# Hardwiring.net
KiCad netlist of a schematic drawn in Altium Designer
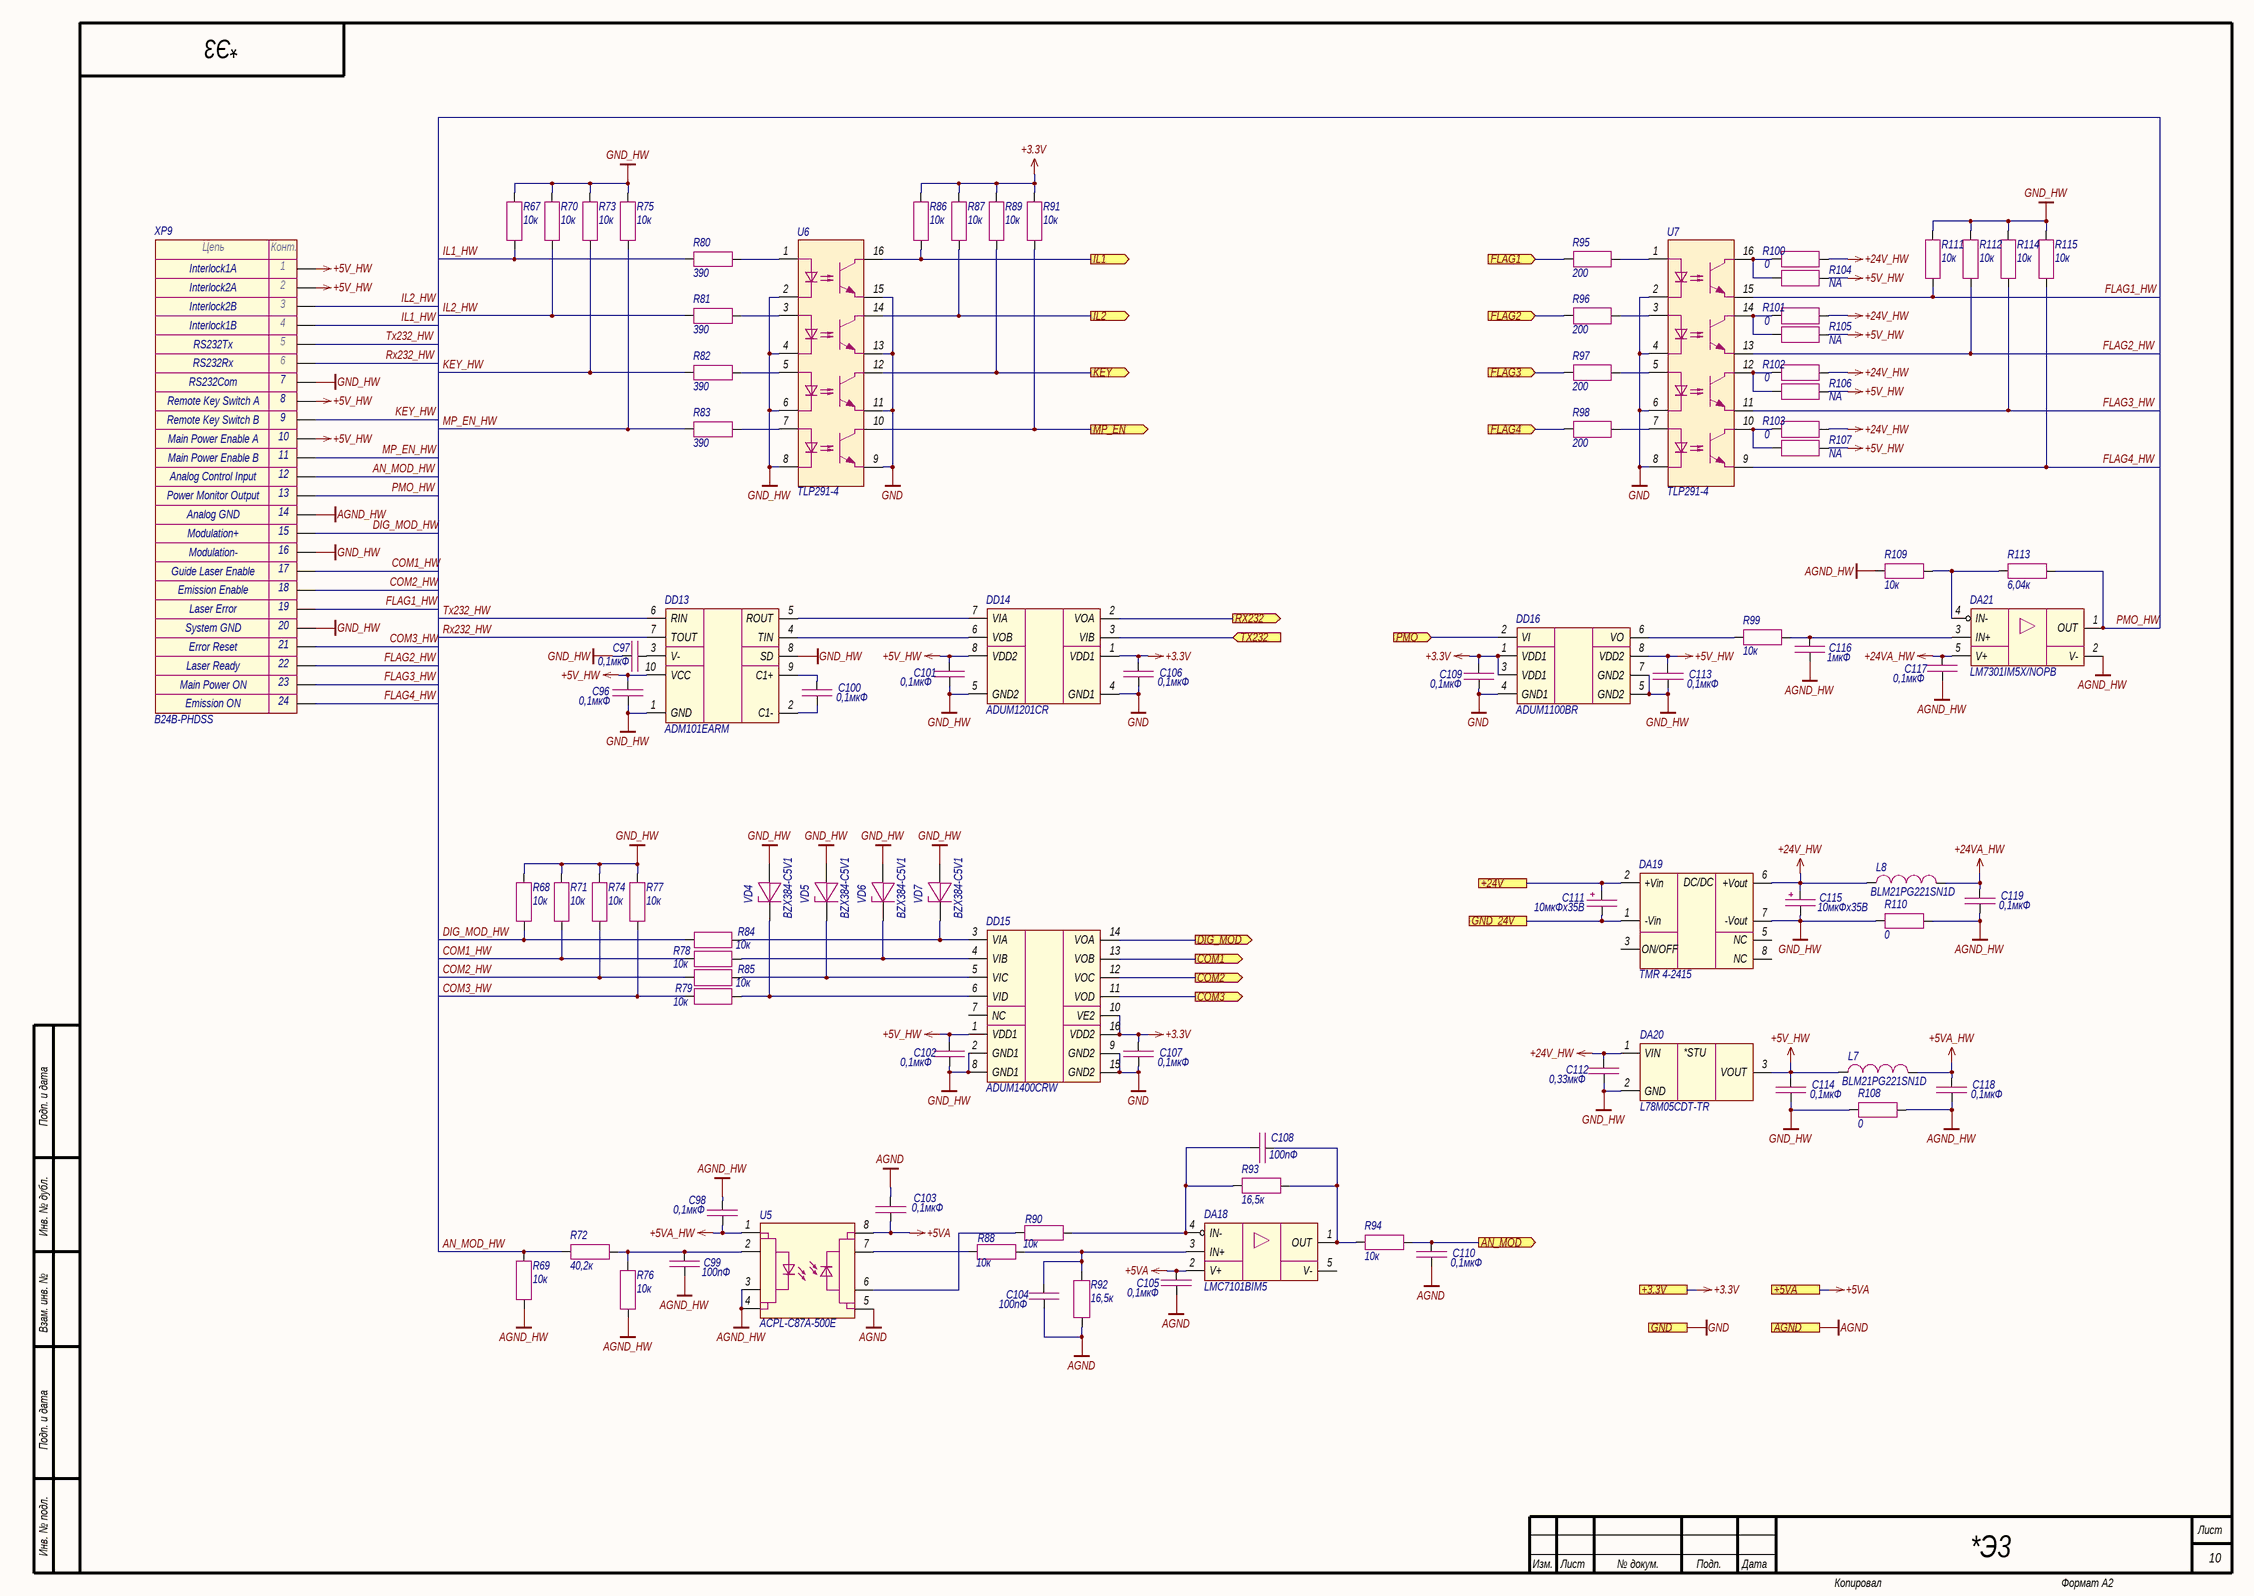
[diagram p0: Hardwiring.SchDoc]

(export (version "E")
  (design (tool "Eeschema 10.0.6"))
  (components
    (comp (ref "C96")
      (value "0,1мкФ")
      (footprint "Pcb_library:CAP_0603")
      (fields (field (name "MANUFACTURER") "Murata"))
      (libsource (lib "Schem_library") (part "Capacitor"))
    )
    (comp (ref "C97")
      (value "0,1мкФ")
      (footprint "Pcb_library:CAP_0603")
      (fields (field (name "MANUFACTURER") "Murata"))
      (libsource (lib "Schem_library") (part "Capacitor"))
    )
    (comp (ref "C98")
      (value "0,1мкФ")
      (footprint "Pcb_library:CAP_0603")
      (fields (field (name "MANUFACTURER") "Murata"))
      (libsource (lib "Schem_library") (part "Capacitor"))
    )
    (comp (ref "C99")
      (value "100пФ")
      (footprint "Pcb_library:CAP_0603")
      (fields (field (name "MANUFACTURER") "Murata"))
      (libsource (lib "Schem_library") (part "Capacitor"))
    )
    (comp (ref "C100")
      (value "0,1мкФ")
      (footprint "Pcb_library:CAP_0603")
      (fields (field (name "MANUFACTURER") "Murata"))
      (libsource (lib "Schem_library") (part "Capacitor"))
    )
    (comp (ref "C101")
      (value "0,1мкФ")
      (footprint "Pcb_library:CAP_0603")
      (fields (field (name "MANUFACTURER") "Murata"))
      (libsource (lib "Schem_library") (part "Capacitor"))
    )
    (comp (ref "C102")
      (value "0,1мкФ")
      (footprint "Pcb_library:CAP_0603")
      (fields (field (name "MANUFACTURER") "Murata"))
      (libsource (lib "Schem_library") (part "Capacitor"))
    )
    (comp (ref "C103")
      (value "0,1мкФ")
      (footprint "Pcb_library:CAP_0603")
      (fields (field (name "MANUFACTURER") "Murata"))
      (libsource (lib "Schem_library") (part "Capacitor"))
    )
    (comp (ref "C104")
      (value "100пФ")
      (footprint "Pcb_library:CAP_0603")
      (fields (field (name "MANUFACTURER") "Murata"))
      (libsource (lib "Schem_library") (part "Capacitor"))
    )
    (comp (ref "C105")
      (value "0,1мкФ")
      (footprint "Pcb_library:CAP_0603")
      (fields (field (name "MANUFACTURER") "Murata"))
      (libsource (lib "Schem_library") (part "Capacitor"))
    )
    (comp (ref "C106")
      (value "0,1мкФ")
      (footprint "Pcb_library:CAP_0603")
      (fields (field (name "MANUFACTURER") "Murata"))
      (libsource (lib "Schem_library") (part "Capacitor"))
    )
    (comp (ref "C107")
      (value "0,1мкФ")
      (footprint "Pcb_library:CAP_0603")
      (fields (field (name "MANUFACTURER") "Murata"))
      (libsource (lib "Schem_library") (part "Capacitor"))
    )
    (comp (ref "C108")
      (value "100пФ")
      (footprint "Pcb_library:CAP_0603")
      (fields (field (name "MANUFACTURER") "Murata"))
      (libsource (lib "Schem_library") (part "Capacitor"))
    )
    (comp (ref "C109")
      (value "0,1мкФ")
      (footprint "Pcb_library:CAP_0603")
      (fields (field (name "MANUFACTURER") "Murata"))
      (libsource (lib "Schem_library") (part "Capacitor"))
    )
    (comp (ref "C110")
      (value "0,1мкФ")
      (footprint "Pcb_library:CAP_0603")
      (fields (field (name "MANUFACTURER") "Murata"))
      (libsource (lib "Schem_library") (part "Capacitor"))
    )
    (comp (ref "C111")
      (value "10мкФх35B")
      (footprint "Pcb_library:CAP_C")
      (libsource (lib "Schem_library") (part "Capacitor_Polar"))
    )
    (comp (ref "C112")
      (value "0,33мкФ")
      (footprint "Pcb_library:CAP_0805")
      (fields (field (name "MANUFACTURER") "Murata"))
      (libsource (lib "Schem_library") (part "Capacitor"))
    )
    (comp (ref "C113")
      (value "0,1мкФ")
      (footprint "Pcb_library:CAP_0603")
      (fields (field (name "MANUFACTURER") "Murata"))
      (libsource (lib "Schem_library") (part "Capacitor"))
    )
    (comp (ref "C114")
      (value "0,1мкФ")
      (footprint "Pcb_library:CAP_0603")
      (fields (field (name "MANUFACTURER") "Murata"))
      (libsource (lib "Schem_library") (part "Capacitor"))
    )
    (comp (ref "C115")
      (value "10мкФх35B")
      (footprint "Pcb_library:CAP_C")
      (libsource (lib "") (part "Capacitor_Polar_1"))
    )
    (comp (ref "C116")
      (value "1мкФ")
      (footprint "Pcb_library:CAP_0603")
      (fields (field (name "MANUFACTURER") "Murata"))
      (libsource (lib "Schem_library") (part "Capacitor"))
    )
    (comp (ref "C117")
      (value "0,1мкФ")
      (footprint "Pcb_library:CAP_0603")
      (fields (field (name "MANUFACTURER") "Murata"))
      (libsource (lib "Schem_library") (part "Capacitor"))
    )
    (comp (ref "C118")
      (value "0,1мкФ")
      (footprint "Pcb_library:CAP_0603")
      (fields (field (name "MANUFACTURER") "Murata"))
      (libsource (lib "Schem_library") (part "Capacitor"))
    )
    (comp (ref "C119")
      (value "0,1мкФ")
      (footprint "Pcb_library:CAP_0603")
      (fields (field (name "MANUFACTURER") "Murata"))
      (libsource (lib "Schem_library") (part "Capacitor"))
    )
    (comp (ref "DA18")
      (value "LMC7101BIM5")
      (footprint "Pcb_library:SOT-23-5")
      (fields (field (name "MANUFACTURER") "Texas Instruments"))
      (libsource (lib "Schem_library") (part "LMC7101"))
    )
    (comp (ref "DA19")
      (value "TMR 4-2415")
      (footprint "Pcb_library:TMR4 (SIP-8)")
      (fields (field (name "MANUFACTURER") "Traco Power"))
      (libsource (lib "Schem_library") (part "TMR4"))
    )
    (comp (ref "DA20")
      (value "L78M05CDT-TR")
      (footprint "Pcb_library:TO-252")
      (fields (field (name "MANUFACTURER") "STMicroelectronics"))
      (libsource (lib "Schem_library") (part "L78M"))
    )
    (comp (ref "DA21")
      (value "LM7301IM5X/NOPB")
      (footprint "Pcb_library:SOT-23-5")
      (fields (field (name "MANUFACTURER") "Texas Instruments"))
      (libsource (lib "Schem_library") (part "LM7301IM5"))
    )
    (comp (ref "DD13")
      (value "ADM101EARM")
      (footprint "Pcb_library:MSOP-10")
      (fields (field (name "MANUFACTURER") "Analog Devices"))
      (libsource (lib "Schem_library") (part "ADM101EARM"))
    )
    (comp (ref "DD14")
      (value "ADUM1201CR")
      (footprint "Pcb_library:SOIC-8")
      (fields (field (name "MANUFACTURER") "Analog Devices"))
      (libsource (lib "Schem_library") (part "ADUM1201"))
    )
    (comp (ref "DD15")
      (value "ADUM1400CRW")
      (footprint "Pcb_library:SOIC-16W")
      (fields (field (name "MANUFACTURER") "Analog Devices"))
      (libsource (lib "Schem_library") (part "ADUM1400"))
    )
    (comp (ref "DD16")
      (value "ADUM1100BR")
      (footprint "Pcb_library:SOIC-8")
      (fields (field (name "MANUFACTURER") "Analog Devices"))
      (libsource (lib "Schem_library") (part "ADUM1100"))
    )
    (comp (ref "L7")
      (value "BLM21PG221SN1D")
      (footprint "Pcb_library:IND_0805")
      (fields (field (name "MANUFACTURER") "Murata"))
      (libsource (lib "Schem_library") (part "Inductor"))
    )
    (comp (ref "L8")
      (value "BLM21PG221SN1D")
      (footprint "Pcb_library:IND_0805")
      (fields (field (name "MANUFACTURER") "Murata"))
      (libsource (lib "Schem_library") (part "Inductor"))
    )
    (comp (ref "R67")
      (value "10к")
      (footprint "Pcb_library:RES_0603")
      (fields (field (name "MANUFACTURER") "Yageo"))
      (libsource (lib "Schem_library") (part "Resistor"))
    )
    (comp (ref "R68")
      (value "10к")
      (footprint "Pcb_library:RES_0603")
      (fields (field (name "MANUFACTURER") "Yageo"))
      (libsource (lib "Schem_library") (part "Resistor"))
    )
    (comp (ref "R69")
      (value "10к")
      (footprint "Pcb_library:RES_0603")
      (fields (field (name "MANUFACTURER") "Yageo"))
      (libsource (lib "Schem_library") (part "Resistor"))
    )
    (comp (ref "R70")
      (value "10к")
      (footprint "Pcb_library:RES_0603")
      (fields (field (name "MANUFACTURER") "Yageo"))
      (libsource (lib "Schem_library") (part "Resistor"))
    )
    (comp (ref "R71")
      (value "10к")
      (footprint "Pcb_library:RES_0603")
      (fields (field (name "MANUFACTURER") "Yageo"))
      (libsource (lib "Schem_library") (part "Resistor"))
    )
    (comp (ref "R72")
      (value "40,2к")
      (footprint "Pcb_library:RES_0603")
      (fields (field (name "MANUFACTURER") "Yageo"))
      (libsource (lib "Schem_library") (part "Resistor"))
    )
    (comp (ref "R73")
      (value "10к")
      (footprint "Pcb_library:RES_0603")
      (fields (field (name "MANUFACTURER") "Yageo"))
      (libsource (lib "Schem_library") (part "Resistor"))
    )
    (comp (ref "R74")
      (value "10к")
      (footprint "Pcb_library:RES_0603")
      (fields (field (name "MANUFACTURER") "Yageo"))
      (libsource (lib "Schem_library") (part "Resistor"))
    )
    (comp (ref "R75")
      (value "10к")
      (footprint "Pcb_library:RES_0603")
      (fields (field (name "MANUFACTURER") "Yageo"))
      (libsource (lib "Schem_library") (part "Resistor"))
    )
    (comp (ref "R76")
      (value "10к")
      (footprint "Pcb_library:RES_0603")
      (fields (field (name "MANUFACTURER") "Yageo"))
      (libsource (lib "Schem_library") (part "Resistor"))
    )
    (comp (ref "R77")
      (value "10к")
      (footprint "Pcb_library:RES_0603")
      (fields (field (name "MANUFACTURER") "Yageo"))
      (libsource (lib "Schem_library") (part "Resistor"))
    )
    (comp (ref "R78")
      (value "10к")
      (footprint "Pcb_library:RES_0603")
      (fields (field (name "MANUFACTURER") "Yageo"))
      (libsource (lib "Schem_library") (part "Resistor"))
    )
    (comp (ref "R79")
      (value "10к")
      (footprint "Pcb_library:RES_0603")
      (fields (field (name "MANUFACTURER") "Yageo"))
      (libsource (lib "Schem_library") (part "Resistor"))
    )
    (comp (ref "R80")
      (value "390")
      (footprint "Pcb_library:RES_0603")
      (fields (field (name "MANUFACTURER") "Yageo"))
      (libsource (lib "Schem_library") (part "Resistor"))
    )
    (comp (ref "R81")
      (value "390")
      (footprint "Pcb_library:RES_0603")
      (fields (field (name "MANUFACTURER") "Yageo"))
      (libsource (lib "Schem_library") (part "Resistor"))
    )
    (comp (ref "R82")
      (value "390")
      (footprint "Pcb_library:RES_0603")
      (fields (field (name "MANUFACTURER") "Yageo"))
      (libsource (lib "Schem_library") (part "Resistor"))
    )
    (comp (ref "R83")
      (value "390")
      (footprint "Pcb_library:RES_0603")
      (fields (field (name "MANUFACTURER") "Yageo"))
      (libsource (lib "Schem_library") (part "Resistor"))
    )
    (comp (ref "R84")
      (value "10к")
      (footprint "Pcb_library:RES_0603")
      (fields (field (name "MANUFACTURER") "Yageo"))
      (libsource (lib "Schem_library") (part "Resistor"))
    )
    (comp (ref "R85")
      (value "10к")
      (footprint "Pcb_library:RES_0603")
      (fields (field (name "MANUFACTURER") "Yageo"))
      (libsource (lib "Schem_library") (part "Resistor"))
    )
    (comp (ref "R86")
      (value "10к")
      (footprint "Pcb_library:RES_0603")
      (fields (field (name "MANUFACTURER") "Yageo"))
      (libsource (lib "Schem_library") (part "Resistor"))
    )
    (comp (ref "R87")
      (value "10к")
      (footprint "Pcb_library:RES_0603")
      (fields (field (name "MANUFACTURER") "Yageo"))
      (libsource (lib "Schem_library") (part "Resistor"))
    )
    (comp (ref "R88")
      (value "10к")
      (footprint "Pcb_library:RES_0603")
      (fields (field (name "MANUFACTURER") "Yageo"))
      (libsource (lib "Schem_library") (part "Resistor"))
    )
    (comp (ref "R89")
      (value "10к")
      (footprint "Pcb_library:RES_0603")
      (fields (field (name "MANUFACTURER") "Yageo"))
      (libsource (lib "Schem_library") (part "Resistor"))
    )
    (comp (ref "R90")
      (value "10к")
      (footprint "Pcb_library:RES_0603")
      (fields (field (name "MANUFACTURER") "Yageo"))
      (libsource (lib "Schem_library") (part "Resistor"))
    )
    (comp (ref "R91")
      (value "10к")
      (footprint "Pcb_library:RES_0603")
      (fields (field (name "MANUFACTURER") "Yageo"))
      (libsource (lib "Schem_library") (part "Resistor"))
    )
    (comp (ref "R92")
      (value "16,5к")
      (footprint "Pcb_library:RES_0603")
      (fields (field (name "MANUFACTURER") "Yageo"))
      (libsource (lib "Schem_library") (part "Resistor"))
    )
    (comp (ref "R93")
      (value "16,5к")
      (footprint "Pcb_library:RES_0603")
      (fields (field (name "MANUFACTURER") "Yageo"))
      (libsource (lib "Schem_library") (part "Resistor"))
    )
    (comp (ref "R94")
      (value "10к")
      (footprint "Pcb_library:RES_0603")
      (fields (field (name "MANUFACTURER") "Yageo"))
      (libsource (lib "Schem_library") (part "Resistor"))
    )
    (comp (ref "R95")
      (value "200")
      (footprint "Pcb_library:RES_0603")
      (fields (field (name "MANUFACTURER") "Yageo"))
      (libsource (lib "Schem_library") (part "Resistor"))
    )
    (comp (ref "R96")
      (value "200")
      (footprint "Pcb_library:RES_0603")
      (fields (field (name "MANUFACTURER") "Yageo"))
      (libsource (lib "Schem_library") (part "Resistor"))
    )
    (comp (ref "R97")
      (value "200")
      (footprint "Pcb_library:RES_0603")
      (fields (field (name "MANUFACTURER") "Yageo"))
      (libsource (lib "Schem_library") (part "Resistor"))
    )
    (comp (ref "R98")
      (value "200")
      (footprint "Pcb_library:RES_0603")
      (fields (field (name "MANUFACTURER") "Yageo"))
      (libsource (lib "Schem_library") (part "Resistor"))
    )
    (comp (ref "R99")
      (value "10к")
      (footprint "Pcb_library:RES_0603")
      (fields (field (name "MANUFACTURER") "Yageo"))
      (libsource (lib "Schem_library") (part "Resistor"))
    )
    (comp (ref "R100")
      (value "0")
      (footprint "Pcb_library:RES_0603")
      (fields (field (name "MANUFACTURER") "Yageo"))
      (libsource (lib "Schem_library") (part "Resistor"))
    )
    (comp (ref "R101")
      (value "0")
      (footprint "Pcb_library:RES_0603")
      (fields (field (name "MANUFACTURER") "Yageo"))
      (libsource (lib "Schem_library") (part "Resistor"))
    )
    (comp (ref "R102")
      (value "0")
      (footprint "Pcb_library:RES_0603")
      (fields (field (name "MANUFACTURER") "Yageo"))
      (libsource (lib "Schem_library") (part "Resistor"))
    )
    (comp (ref "R103")
      (value "0")
      (footprint "Pcb_library:RES_0603")
      (fields (field (name "MANUFACTURER") "Yageo"))
      (libsource (lib "Schem_library") (part "Resistor"))
    )
    (comp (ref "R104")
      (value "NA")
      (footprint "Pcb_library:RES_0603")
      (libsource (lib "Schem_library") (part "Resistor"))
    )
    (comp (ref "R105")
      (value "NA")
      (footprint "Pcb_library:RES_0603")
      (libsource (lib "Schem_library") (part "Resistor"))
    )
    (comp (ref "R106")
      (value "NA")
      (footprint "Pcb_library:RES_0603")
      (libsource (lib "Schem_library") (part "Resistor"))
    )
    (comp (ref "R107")
      (value "NA")
      (footprint "Pcb_library:RES_0603")
      (libsource (lib "Schem_library") (part "Resistor"))
    )
    (comp (ref "R108")
      (value "0")
      (footprint "Pcb_library:RES_0805")
      (fields (field (name "MANUFACTURER") "Yageo"))
      (libsource (lib "Schem_library") (part "Resistor"))
    )
    (comp (ref "R109")
      (value "10к")
      (footprint "Pcb_library:RES_0603")
      (fields (field (name "MANUFACTURER") "Yageo"))
      (libsource (lib "Schem_library") (part "Resistor"))
    )
    (comp (ref "R110")
      (value "0")
      (footprint "Pcb_library:RES_0805")
      (fields (field (name "MANUFACTURER") "Yageo"))
      (libsource (lib "Schem_library") (part "Resistor"))
    )
    (comp (ref "R111")
      (value "10к")
      (footprint "Pcb_library:RES_0603")
      (fields (field (name "MANUFACTURER") "Yageo"))
      (libsource (lib "Schem_library") (part "Resistor"))
    )
    (comp (ref "R112")
      (value "10к")
      (footprint "Pcb_library:RES_0603")
      (fields (field (name "MANUFACTURER") "Yageo"))
      (libsource (lib "Schem_library") (part "Resistor"))
    )
    (comp (ref "R113")
      (value "6,04к")
      (footprint "Pcb_library:RES_0603")
      (fields (field (name "MANUFACTURER") "Yageo"))
      (libsource (lib "Schem_library") (part "Resistor"))
    )
    (comp (ref "R114")
      (value "10к")
      (footprint "Pcb_library:RES_0603")
      (fields (field (name "MANUFACTURER") "Yageo"))
      (libsource (lib "Schem_library") (part "Resistor"))
    )
    (comp (ref "R115")
      (value "10к")
      (footprint "Pcb_library:RES_0603")
      (fields (field (name "MANUFACTURER") "Yageo"))
      (libsource (lib "Schem_library") (part "Resistor"))
    )
    (comp (ref "U5")
      (value "ACPL-C87A-500E")
      (footprint "Pcb_library:SSO-8")
      (fields (field (name "MANUFACTURER") "Broadcom"))
      (libsource (lib "Schem_library") (part "ACPL-C87"))
    )
    (comp (ref "U6")
      (value "TLP291-4")
      (footprint "Pcb_library:SOP-16")
      (fields (field (name "MANUFACTURER") "Toshiba"))
      (libsource (lib "Schem_library") (part "TLP281-4"))
    )
    (comp (ref "U7")
      (value "TLP291-4")
      (footprint "Pcb_library:SOP-16")
      (fields (field (name "MANUFACTURER") "Toshiba"))
      (libsource (lib "Schem_library") (part "TLP281-4"))
    )
    (comp (ref "VD4")
      (value "BZX384-C5V1")
      (footprint "Pcb_library:SOD-323")
      (fields (field (name "MANUFACTURER") "Nexperia"))
      (libsource (lib "Schem_library") (part "Diode_Zener"))
    )
    (comp (ref "VD5")
      (value "BZX384-C5V1")
      (footprint "Pcb_library:SOD-323")
      (fields (field (name "MANUFACTURER") "Nexperia"))
      (libsource (lib "Schem_library") (part "Diode_Zener"))
    )
    (comp (ref "VD6")
      (value "BZX384-C5V1")
      (footprint "Pcb_library:SOD-323")
      (fields (field (name "MANUFACTURER") "Nexperia"))
      (libsource (lib "Schem_library") (part "Diode_Zener"))
    )
    (comp (ref "VD7")
      (value "BZX384-C5V1")
      (footprint "Pcb_library:SOD-323")
      (fields (field (name "MANUFACTURER") "Nexperia"))
      (libsource (lib "Schem_library") (part "Diode_Zener"))
    )
    (comp (ref "XP9")
      (value "B24B-PHDSS")
      (footprint "Pcb_library:B24B-PHDSS")
      (fields (field (name "MANUFACTURER") "JST"))
      (libsource (lib "Schem_library") (part "Connector-24"))
    )
  )
  (nets
    (net (code "1") (name "+3.3V") (class "Default")
      (node (ref "C106") (pin "1") (pinfunction "1_1") (pintype "passive"))
      (node (ref "C107") (pin "1") (pinfunction "1_1") (pintype "passive"))
      (node (ref "C109") (pin "1") (pinfunction "1_1") (pintype "passive"))
      (node (ref "DD14") (pin "1") (pinfunction "VDD1_1") (pintype "passive"))
      (node (ref "DD15") (pin "10") (pinfunction "VE2_10") (pintype "passive"))
      (node (ref "DD15") (pin "16") (pinfunction "VDD2_16") (pintype "passive"))
      (node (ref "DD16") (pin "1") (pinfunction "VDD1_1") (pintype "passive"))
      (node (ref "DD16") (pin "3") (pinfunction "VDD1_3") (pintype "passive"))
      (node (ref "R86") (pin "1") (pinfunction "1_1") (pintype "passive"))
      (node (ref "R87") (pin "1") (pinfunction "1_1") (pintype "passive"))
      (node (ref "R89") (pin "1") (pinfunction "1_1") (pintype "passive"))
      (node (ref "R91") (pin "1") (pinfunction "1_1") (pintype "passive"))
    )
    (net (code "2") (name "+5VA") (class "Default")
      (node (ref "C103") (pin "1") (pinfunction "1_1") (pintype "passive"))
      (node (ref "C105") (pin "1") (pinfunction "1_1") (pintype "passive"))
      (node (ref "DA18") (pin "2") (pinfunction "V+_2") (pintype "passive"))
      (node (ref "U5") (pin "8") (pinfunction "VDD2_8") (pintype "passive"))
    )
    (net (code "3") (name "+5VA_HW") (class "Default")
      (node (ref "C118") (pin "1") (pinfunction "1_1") (pintype "passive"))
      (node (ref "C98") (pin "1") (pinfunction "1_1") (pintype "passive"))
      (node (ref "L7") (pin "2") (pinfunction "2_2") (pintype "passive"))
      (node (ref "U5") (pin "1") (pinfunction "VDD1_1") (pintype "passive"))
    )
    (net (code "4") (name "+5V_HW") (class "Default")
      (node (ref "C101") (pin "1") (pinfunction "1_1") (pintype "passive"))
      (node (ref "C102") (pin "1") (pinfunction "1_1") (pintype "passive"))
      (node (ref "C113") (pin "1") (pinfunction "1_1") (pintype "passive"))
      (node (ref "C114") (pin "1") (pinfunction "1_1") (pintype "passive"))
      (node (ref "C96") (pin "1") (pinfunction "1_1") (pintype "passive"))
      (node (ref "DA20") (pin "3") (pinfunction "VOUT_3") (pintype "passive"))
      (node (ref "DD13") (pin "10") (pinfunction "VCC_10") (pintype "passive"))
      (node (ref "DD14") (pin "8") (pinfunction "VDD2_8") (pintype "passive"))
      (node (ref "DD15") (pin "1") (pinfunction "VDD1_1") (pintype "passive"))
      (node (ref "DD16") (pin "8") (pinfunction "VDD2_8") (pintype "passive"))
      (node (ref "L7") (pin "1") (pinfunction "1_1") (pintype "passive"))
      (node (ref "R104") (pin "2") (pinfunction "2_2") (pintype "passive"))
      (node (ref "R105") (pin "2") (pinfunction "2_2") (pintype "passive"))
      (node (ref "R106") (pin "2") (pinfunction "2_2") (pintype "passive"))
      (node (ref "R107") (pin "2") (pinfunction "2_2") (pintype "passive"))
      (node (ref "XP9") (pin "1") (pintype "passive"))
      (node (ref "XP9") (pin "10") (pintype "passive"))
      (node (ref "XP9") (pin "2") (pintype "passive"))
      (node (ref "XP9") (pin "8") (pintype "passive"))
    )
    (net (code "5") (name "+24VA_HW") (class "Default")
      (node (ref "C117") (pin "1") (pinfunction "1_1") (pintype "passive"))
      (node (ref "C119") (pin "1") (pinfunction "1_1") (pintype "passive"))
      (node (ref "DA21") (pin "5") (pinfunction "V+_5") (pintype "passive"))
      (node (ref "L8") (pin "2") (pinfunction "2_2") (pintype "passive"))
    )
    (net (code "6") (name "+24V_HW") (class "Default")
      (node (ref "C112") (pin "2") (pinfunction "2_2") (pintype "passive"))
      (node (ref "C115") (pin "1") (pinfunction "1_1") (pintype "passive"))
      (node (ref "DA19") (pin "6") (pinfunction "+Vout_6") (pintype "passive"))
      (node (ref "DA20") (pin "1") (pinfunction "VIN_1") (pintype "passive"))
      (node (ref "L8") (pin "1") (pinfunction "1_1") (pintype "passive"))
      (node (ref "R100") (pin "2") (pinfunction "2_2") (pintype "passive"))
      (node (ref "R101") (pin "2") (pinfunction "2_2") (pintype "passive"))
      (node (ref "R102") (pin "2") (pinfunction "2_2") (pintype "passive"))
      (node (ref "R103") (pin "2") (pinfunction "2_2") (pintype "passive"))
    )
    (net (code "7") (name "/+24V") (class "Default")
      (node (ref "C111") (pin "1") (pinfunction "1_1") (pintype "passive"))
      (node (ref "DA19") (pin "2") (pinfunction "+Vin_2") (pintype "passive"))
    )
    (net (code "8") (name "/AN_MOD") (class "Default")
      (node (ref "C110") (pin "1") (pinfunction "1_1") (pintype "passive"))
      (node (ref "R94") (pin "2") (pinfunction "2_2") (pintype "passive"))
    )
    (net (code "9") (name "/AN_MOD_HW") (class "Default")
      (node (ref "R69") (pin "1") (pinfunction "1_1") (pintype "passive"))
      (node (ref "R72") (pin "2") (pinfunction "2_2") (pintype "passive"))
      (node (ref "XP9") (pin "12") (pintype "passive"))
    )
    (net (code "10") (name "/COM1") (class "Default")
      (node (ref "DD15") (pin "13") (pinfunction "VOB_13") (pintype "passive"))
    )
    (net (code "11") (name "/COM1_HW") (class "Default")
      (node (ref "R71") (pin "2") (pinfunction "2_2") (pintype "passive"))
      (node (ref "R78") (pin "1") (pinfunction "1_1") (pintype "passive"))
      (node (ref "XP9") (pin "17") (pintype "passive"))
    )
    (net (code "12") (name "/COM2") (class "Default")
      (node (ref "DD15") (pin "12") (pinfunction "VOC_12") (pintype "passive"))
    )
    (net (code "13") (name "/COM2_HW") (class "Default")
      (node (ref "R74") (pin "2") (pinfunction "2_2") (pintype "passive"))
      (node (ref "R85") (pin "1") (pinfunction "1_1") (pintype "passive"))
      (node (ref "XP9") (pin "18") (pintype "passive"))
    )
    (net (code "14") (name "/COM3") (class "Default")
      (node (ref "DD15") (pin "11") (pinfunction "VOD_11") (pintype "passive"))
    )
    (net (code "15") (name "/COM3_HW") (class "Default")
      (node (ref "R77") (pin "2") (pinfunction "2_2") (pintype "passive"))
      (node (ref "R79") (pin "1") (pinfunction "1_1") (pintype "passive"))
      (node (ref "XP9") (pin "21") (pintype "passive"))
    )
    (net (code "16") (name "/DIG_MOD") (class "Default")
      (node (ref "DD15") (pin "14") (pinfunction "VOA_14") (pintype "passive"))
    )
    (net (code "17") (name "/DIG_MOD_HW") (class "Default")
      (node (ref "R68") (pin "2") (pinfunction "2_2") (pintype "passive"))
      (node (ref "R84") (pin "1") (pinfunction "1_1") (pintype "passive"))
      (node (ref "XP9") (pin "15") (pintype "passive"))
    )
    (net (code "18") (name "/FLAG1") (class "Default")
      (node (ref "R95") (pin "2") (pinfunction "2_2") (pintype "passive"))
    )
    (net (code "19") (name "/FLAG1_HW") (class "Default")
      (node (ref "R111") (pin "2") (pinfunction "2_2") (pintype "passive"))
      (node (ref "U7") (pin "15") (pintype "passive"))
      (node (ref "XP9") (pin "19") (pintype "passive"))
    )
    (net (code "20") (name "/FLAG2") (class "Default")
      (node (ref "R96") (pin "2") (pinfunction "2_2") (pintype "passive"))
    )
    (net (code "21") (name "/FLAG2_HW") (class "Default")
      (node (ref "R112") (pin "2") (pinfunction "2_2") (pintype "passive"))
      (node (ref "U7") (pin "13") (pintype "passive"))
      (node (ref "XP9") (pin "22") (pintype "passive"))
    )
    (net (code "22") (name "/FLAG3") (class "Default")
      (node (ref "R97") (pin "2") (pinfunction "2_2") (pintype "passive"))
    )
    (net (code "23") (name "/FLAG3_HW") (class "Default")
      (node (ref "R114") (pin "2") (pinfunction "2_2") (pintype "passive"))
      (node (ref "U7") (pin "11") (pintype "passive"))
      (node (ref "XP9") (pin "23") (pintype "passive"))
    )
    (net (code "24") (name "/FLAG4") (class "Default")
      (node (ref "R98") (pin "2") (pinfunction "2_2") (pintype "passive"))
    )
    (net (code "25") (name "/FLAG4_HW") (class "Default")
      (node (ref "R115") (pin "2") (pinfunction "2_2") (pintype "passive"))
      (node (ref "U7") (pin "9") (pintype "passive"))
      (node (ref "XP9") (pin "24") (pintype "passive"))
    )
    (net (code "26") (name "/GND_24V") (class "Default")
      (node (ref "C111") (pin "2") (pinfunction "2_2") (pintype "passive"))
      (node (ref "DA19") (pin "1") (pinfunction "-Vin_1") (pintype "passive"))
    )
    (net (code "27") (name "/IL1") (class "Default")
      (node (ref "R86") (pin "2") (pinfunction "2_2") (pintype "passive"))
      (node (ref "U6") (pin "16") (pintype "passive"))
    )
    (net (code "28") (name "/IL1_HW") (class "Default")
      (node (ref "R67") (pin "2") (pinfunction "2_2") (pintype "passive"))
      (node (ref "R80") (pin "1") (pinfunction "1_1") (pintype "passive"))
      (node (ref "XP9") (pin "4") (pintype "passive"))
    )
    (net (code "29") (name "/IL2") (class "Default")
      (node (ref "R87") (pin "2") (pinfunction "2_2") (pintype "passive"))
      (node (ref "U6") (pin "14") (pintype "passive"))
    )
    (net (code "30") (name "/IL2_HW") (class "Default")
      (node (ref "R70") (pin "2") (pinfunction "2_2") (pintype "passive"))
      (node (ref "R81") (pin "1") (pinfunction "1_1") (pintype "passive"))
      (node (ref "XP9") (pin "3") (pintype "passive"))
    )
    (net (code "31") (name "/KEY") (class "Default")
      (node (ref "R89") (pin "2") (pinfunction "2_2") (pintype "passive"))
      (node (ref "U6") (pin "12") (pintype "passive"))
    )
    (net (code "32") (name "/KEY_HW") (class "Default")
      (node (ref "R73") (pin "2") (pinfunction "2_2") (pintype "passive"))
      (node (ref "R82") (pin "1") (pinfunction "1_1") (pintype "passive"))
      (node (ref "XP9") (pin "9") (pintype "passive"))
    )
    (net (code "33") (name "/MP_EN") (class "Default")
      (node (ref "R91") (pin "2") (pinfunction "2_2") (pintype "passive"))
      (node (ref "U6") (pin "10") (pintype "passive"))
    )
    (net (code "34") (name "/MP_EN_HW") (class "Default")
      (node (ref "R75") (pin "2") (pinfunction "2_2") (pintype "passive"))
      (node (ref "R83") (pin "1") (pinfunction "1_1") (pintype "passive"))
      (node (ref "XP9") (pin "11") (pintype "passive"))
    )
    (net (code "35") (name "/PMO") (class "Default")
      (node (ref "DD16") (pin "2") (pinfunction "VI_2") (pintype "passive"))
    )
    (net (code "36") (name "/PMO_HW") (class "Default")
      (node (ref "DA21") (pin "1") (pinfunction "OUT_1") (pintype "passive"))
      (node (ref "R113") (pin "2") (pinfunction "2_2") (pintype "passive"))
      (node (ref "XP9") (pin "13") (pintype "passive"))
    )
    (net (code "37") (name "/RX232") (class "Default")
      (node (ref "DD14") (pin "2") (pinfunction "VOA_2") (pintype "passive"))
    )
    (net (code "38") (name "/Rx232_HW") (class "Default")
      (node (ref "DD13") (pin "7") (pinfunction "TOUT_7") (pintype "passive"))
      (node (ref "XP9") (pin "6") (pintype "passive"))
    )
    (net (code "39") (name "/TX232") (class "Default")
      (node (ref "DD14") (pin "3") (pinfunction "VIB_3") (pintype "passive"))
    )
    (net (code "40") (name "/Tx232_HW") (class "Default")
      (node (ref "DD13") (pin "6") (pinfunction "RIN_6") (pintype "passive"))
      (node (ref "XP9") (pin "5") (pintype "passive"))
    )
    (net (code "41") (name "AGND") (class "Default")
      (node (ref "C103") (pin "2") (pinfunction "2_2") (pintype "passive"))
      (node (ref "C104") (pin "2") (pinfunction "2_2") (pintype "passive"))
      (node (ref "C105") (pin "2") (pinfunction "2_2") (pintype "passive"))
      (node (ref "C110") (pin "2") (pinfunction "2_2") (pintype "passive"))
      (node (ref "R92") (pin "2") (pinfunction "2_2") (pintype "passive"))
      (node (ref "U5") (pin "5") (pinfunction "GND2_5") (pintype "passive"))
    )
    (net (code "42") (name "AGND_HW") (class "Default")
      (node (ref "C116") (pin "2") (pinfunction "2_2") (pintype "passive"))
      (node (ref "C117") (pin "2") (pinfunction "2_2") (pintype "passive"))
      (node (ref "C118") (pin "2") (pinfunction "2_2") (pintype "passive"))
      (node (ref "C119") (pin "2") (pinfunction "2_2") (pintype "passive"))
      (node (ref "C98") (pin "2") (pinfunction "2_2") (pintype "passive"))
      (node (ref "C99") (pin "1") (pinfunction "1_1") (pintype "passive"))
      (node (ref "DA21") (pin "2") (pinfunction "V-_2") (pintype "passive"))
      (node (ref "R108") (pin "2") (pinfunction "2_2") (pintype "passive"))
      (node (ref "R109") (pin "1") (pinfunction "1_1") (pintype "passive"))
      (node (ref "R110") (pin "2") (pinfunction "2_2") (pintype "passive"))
      (node (ref "R69") (pin "2") (pinfunction "2_2") (pintype "passive"))
      (node (ref "R76") (pin "2") (pinfunction "2_2") (pintype "passive"))
      (node (ref "U5") (pin "3") (pinfunction "SHDN_3") (pintype "passive"))
      (node (ref "U5") (pin "4") (pinfunction "GND1_4") (pintype "passive"))
      (node (ref "XP9") (pin "14") (pintype "passive"))
    )
    (net (code "43") (name "GND") (class "Default")
      (node (ref "C106") (pin "2") (pinfunction "2_2") (pintype "passive"))
      (node (ref "C107") (pin "2") (pinfunction "2_2") (pintype "passive"))
      (node (ref "C109") (pin "2") (pinfunction "2_2") (pintype "passive"))
      (node (ref "DD14") (pin "4") (pinfunction "GND1_4") (pintype "passive"))
      (node (ref "DD15") (pin "15") (pinfunction "GND2_15") (pintype "passive"))
      (node (ref "DD15") (pin "9") (pinfunction "GND2_9") (pintype "passive"))
      (node (ref "DD16") (pin "4") (pinfunction "GND1_4") (pintype "passive"))
      (node (ref "U6") (pin "11") (pintype "passive"))
      (node (ref "U6") (pin "13") (pintype "passive"))
      (node (ref "U6") (pin "15") (pintype "passive"))
      (node (ref "U6") (pin "9") (pintype "passive"))
      (node (ref "U7") (pin "2") (pintype "passive"))
      (node (ref "U7") (pin "4") (pintype "passive"))
      (node (ref "U7") (pin "6") (pintype "passive"))
      (node (ref "U7") (pin "8") (pintype "passive"))
    )
    (net (code "44") (name "GND_HW") (class "Default")
      (node (ref "C101") (pin "2") (pinfunction "2_2") (pintype "passive"))
      (node (ref "C102") (pin "2") (pinfunction "2_2") (pintype "passive"))
      (node (ref "C112") (pin "1") (pinfunction "1_1") (pintype "passive"))
      (node (ref "C113") (pin "2") (pinfunction "2_2") (pintype "passive"))
      (node (ref "C114") (pin "2") (pinfunction "2_2") (pintype "passive"))
      (node (ref "C115") (pin "2") (pinfunction "2_2") (pintype "passive"))
      (node (ref "C96") (pin "2") (pinfunction "2_2") (pintype "passive"))
      (node (ref "C97") (pin "2") (pinfunction "2_2") (pintype "passive"))
      (node (ref "DA19") (pin "7") (pinfunction "-Vout_7") (pintype "passive"))
      (node (ref "DA20") (pin "2") (pinfunction "GND_2") (pintype "passive"))
      (node (ref "DD13") (pin "1") (pinfunction "GND_1") (pintype "passive"))
      (node (ref "DD13") (pin "8") (pinfunction "SD_8") (pintype "passive"))
      (node (ref "DD14") (pin "5") (pinfunction "GND2_5") (pintype "passive"))
      (node (ref "DD15") (pin "2") (pinfunction "GND1_2") (pintype "passive"))
      (node (ref "DD15") (pin "8") (pinfunction "GND1_8") (pintype "passive"))
      (node (ref "DD16") (pin "5") (pinfunction "GND2_5") (pintype "passive"))
      (node (ref "DD16") (pin "7") (pinfunction "GND2_7") (pintype "passive"))
      (node (ref "R108") (pin "1") (pinfunction "1_1") (pintype "passive"))
      (node (ref "R110") (pin "1") (pinfunction "1_1") (pintype "passive"))
      (node (ref "R111") (pin "1") (pinfunction "1_1") (pintype "passive"))
      (node (ref "R112") (pin "1") (pinfunction "1_1") (pintype "passive"))
      (node (ref "R114") (pin "1") (pinfunction "1_1") (pintype "passive"))
      (node (ref "R115") (pin "1") (pinfunction "1_1") (pintype "passive"))
      (node (ref "R67") (pin "1") (pinfunction "1_1") (pintype "passive"))
      (node (ref "R68") (pin "1") (pinfunction "1_1") (pintype "passive"))
      (node (ref "R70") (pin "1") (pinfunction "1_1") (pintype "passive"))
      (node (ref "R71") (pin "1") (pinfunction "1_1") (pintype "passive"))
      (node (ref "R73") (pin "1") (pinfunction "1_1") (pintype "passive"))
      (node (ref "R74") (pin "1") (pinfunction "1_1") (pintype "passive"))
      (node (ref "R75") (pin "1") (pinfunction "1_1") (pintype "passive"))
      (node (ref "R77") (pin "1") (pinfunction "1_1") (pintype "passive"))
      (node (ref "U6") (pin "2") (pintype "passive"))
      (node (ref "U6") (pin "4") (pintype "passive"))
      (node (ref "U6") (pin "6") (pintype "passive"))
      (node (ref "U6") (pin "8") (pintype "passive"))
      (node (ref "VD4") (pin "2") (pinfunction "A_2") (pintype "passive"))
      (node (ref "VD5") (pin "2") (pinfunction "A_2") (pintype "passive"))
      (node (ref "VD6") (pin "2") (pinfunction "A_2") (pintype "passive"))
      (node (ref "VD7") (pin "2") (pinfunction "A_2") (pintype "passive"))
      (node (ref "XP9") (pin "16") (pintype "passive"))
      (node (ref "XP9") (pin "20") (pintype "passive"))
      (node (ref "XP9") (pin "7") (pintype "passive"))
    )
    (net (code "45") (name "Net-(DA18-IN+)") (class "Default")
      (node (ref "C104") (pin "1") (pinfunction "1_1") (pintype "passive"))
      (node (ref "DA18") (pin "3") (pinfunction "IN+_3") (pintype "passive"))
      (node (ref "R88") (pin "2") (pinfunction "2_2") (pintype "passive"))
      (node (ref "R92") (pin "1") (pinfunction "1_1") (pintype "passive"))
    )
    (net (code "46") (name "Net-(DA18-IN-)") (class "Default")
      (node (ref "C108") (pin "1") (pinfunction "1_1") (pintype "passive"))
      (node (ref "DA18") (pin "4") (pinfunction "IN-_4") (pintype "passive"))
      (node (ref "R90") (pin "2") (pinfunction "2_2") (pintype "passive"))
      (node (ref "R93") (pin "2") (pinfunction "2_2") (pintype "passive"))
    )
    (net (code "47") (name "Net-(DA18-OUT)") (class "Default")
      (node (ref "C108") (pin "2") (pinfunction "2_2") (pintype "passive"))
      (node (ref "DA18") (pin "1") (pinfunction "OUT_1") (pintype "passive"))
      (node (ref "R93") (pin "1") (pinfunction "1_1") (pintype "passive"))
      (node (ref "R94") (pin "1") (pinfunction "1_1") (pintype "passive"))
    )
    (net (code "48") (name "Net-(DA21-IN+)") (class "Default")
      (node (ref "C116") (pin "1") (pinfunction "1_1") (pintype "passive"))
      (node (ref "DA21") (pin "3") (pinfunction "IN+_3") (pintype "passive"))
      (node (ref "R99") (pin "2") (pinfunction "2_2") (pintype "passive"))
    )
    (net (code "49") (name "Net-(DA21-IN-)") (class "Default")
      (node (ref "DA21") (pin "4") (pinfunction "IN-_4") (pintype "passive"))
      (node (ref "R109") (pin "2") (pinfunction "2_2") (pintype "passive"))
      (node (ref "R113") (pin "1") (pinfunction "1_1") (pintype "passive"))
    )
    (net (code "50") (name "Net-(DD13-C1+)") (class "Default")
      (node (ref "C100") (pin "1") (pinfunction "1_1") (pintype "passive"))
      (node (ref "DD13") (pin "9") (pinfunction "C1+_9") (pintype "passive"))
    )
    (net (code "51") (name "Net-(DD13-C1-)") (class "Default")
      (node (ref "C100") (pin "2") (pinfunction "2_2") (pintype "passive"))
      (node (ref "DD13") (pin "2") (pinfunction "C1-_2") (pintype "passive"))
    )
    (net (code "52") (name "Net-(DD13-ROUT)") (class "Default")
      (node (ref "DD13") (pin "5") (pinfunction "ROUT_5") (pintype "passive"))
      (node (ref "DD14") (pin "7") (pinfunction "VIA_7") (pintype "passive"))
    )
    (net (code "53") (name "Net-(DD13-TIN)") (class "Default")
      (node (ref "DD13") (pin "4") (pinfunction "TIN_4") (pintype "passive"))
      (node (ref "DD14") (pin "6") (pinfunction "VOB_6") (pintype "passive"))
    )
    (net (code "54") (name "Net-(DD13-V-)") (class "Default")
      (node (ref "C97") (pin "1") (pinfunction "1_1") (pintype "passive"))
      (node (ref "DD13") (pin "3") (pinfunction "V-_3") (pintype "passive"))
    )
    (net (code "55") (name "Net-(DD15-VIA)") (class "Default")
      (node (ref "DD15") (pin "3") (pinfunction "VIA_3") (pintype "passive"))
      (node (ref "R84") (pin "2") (pinfunction "2_2") (pintype "passive"))
      (node (ref "VD7") (pin "1") (pinfunction "K_1") (pintype "passive"))
    )
    (net (code "56") (name "Net-(DD15-VIB)") (class "Default")
      (node (ref "DD15") (pin "4") (pinfunction "VIB_4") (pintype "passive"))
      (node (ref "R78") (pin "2") (pinfunction "2_2") (pintype "passive"))
      (node (ref "VD6") (pin "1") (pinfunction "K_1") (pintype "passive"))
    )
    (net (code "57") (name "Net-(DD15-VIC)") (class "Default")
      (node (ref "DD15") (pin "5") (pinfunction "VIC_5") (pintype "passive"))
      (node (ref "R85") (pin "2") (pinfunction "2_2") (pintype "passive"))
      (node (ref "VD5") (pin "1") (pinfunction "K_1") (pintype "passive"))
    )
    (net (code "58") (name "Net-(DD15-VID)") (class "Default")
      (node (ref "DD15") (pin "6") (pinfunction "VID_6") (pintype "passive"))
      (node (ref "R79") (pin "2") (pinfunction "2_2") (pintype "passive"))
      (node (ref "VD4") (pin "1") (pinfunction "K_1") (pintype "passive"))
    )
    (net (code "59") (name "Net-(DD16-VO)") (class "Default")
      (node (ref "DD16") (pin "6") (pinfunction "VO_6") (pintype "passive"))
      (node (ref "R99") (pin "1") (pinfunction "1_1") (pintype "passive"))
    )
    (net (code "60") (name "Net-(R80-Pad2)") (class "Default")
      (node (ref "R80") (pin "2") (pinfunction "2_2") (pintype "passive"))
      (node (ref "U6") (pin "1") (pintype "passive"))
    )
    (net (code "61") (name "Net-(R81-Pad2)") (class "Default")
      (node (ref "R81") (pin "2") (pinfunction "2_2") (pintype "passive"))
      (node (ref "U6") (pin "3") (pintype "passive"))
    )
    (net (code "62") (name "Net-(R82-Pad2)") (class "Default")
      (node (ref "R82") (pin "2") (pinfunction "2_2") (pintype "passive"))
      (node (ref "U6") (pin "5") (pintype "passive"))
    )
    (net (code "63") (name "Net-(R83-Pad2)") (class "Default")
      (node (ref "R83") (pin "2") (pinfunction "2_2") (pintype "passive"))
      (node (ref "U6") (pin "7") (pintype "passive"))
    )
    (net (code "64") (name "Net-(R95-Pad1)") (class "Default")
      (node (ref "R95") (pin "1") (pinfunction "1_1") (pintype "passive"))
      (node (ref "U7") (pin "1") (pintype "passive"))
    )
    (net (code "65") (name "Net-(R96-Pad1)") (class "Default")
      (node (ref "R96") (pin "1") (pinfunction "1_1") (pintype "passive"))
      (node (ref "U7") (pin "3") (pintype "passive"))
    )
    (net (code "66") (name "Net-(R97-Pad1)") (class "Default")
      (node (ref "R97") (pin "1") (pinfunction "1_1") (pintype "passive"))
      (node (ref "U7") (pin "5") (pintype "passive"))
    )
    (net (code "67") (name "Net-(R98-Pad1)") (class "Default")
      (node (ref "R98") (pin "1") (pinfunction "1_1") (pintype "passive"))
      (node (ref "U7") (pin "7") (pintype "passive"))
    )
    (net (code "68") (name "Net-(R100-Pad1)") (class "Default")
      (node (ref "R100") (pin "1") (pinfunction "1_1") (pintype "passive"))
      (node (ref "R104") (pin "1") (pinfunction "1_1") (pintype "passive"))
      (node (ref "U7") (pin "16") (pintype "passive"))
    )
    (net (code "69") (name "Net-(R101-Pad1)") (class "Default")
      (node (ref "R101") (pin "1") (pinfunction "1_1") (pintype "passive"))
      (node (ref "R105") (pin "1") (pinfunction "1_1") (pintype "passive"))
      (node (ref "U7") (pin "14") (pintype "passive"))
    )
    (net (code "70") (name "Net-(R102-Pad1)") (class "Default")
      (node (ref "R102") (pin "1") (pinfunction "1_1") (pintype "passive"))
      (node (ref "R106") (pin "1") (pinfunction "1_1") (pintype "passive"))
      (node (ref "U7") (pin "12") (pintype "passive"))
    )
    (net (code "71") (name "Net-(R103-Pad1)") (class "Default")
      (node (ref "R103") (pin "1") (pinfunction "1_1") (pintype "passive"))
      (node (ref "R107") (pin "1") (pinfunction "1_1") (pintype "passive"))
      (node (ref "U7") (pin "10") (pintype "passive"))
    )
    (net (code "72") (name "Net-(U5-VIN)") (class "Default")
      (node (ref "C99") (pin "2") (pinfunction "2_2") (pintype "passive"))
      (node (ref "R72") (pin "1") (pinfunction "1_1") (pintype "passive"))
      (node (ref "R76") (pin "1") (pinfunction "1_1") (pintype "passive"))
      (node (ref "U5") (pin "2") (pinfunction "VIN_2") (pintype "passive"))
    )
    (net (code "73") (name "Net-(U5-VOUT+)") (class "Default")
      (node (ref "R88") (pin "1") (pinfunction "1_1") (pintype "passive"))
      (node (ref "U5") (pin "7") (pinfunction "VOUT+_7") (pintype "passive"))
    )
    (net (code "74") (name "Net-(U5-VOUT-)") (class "Default")
      (node (ref "R90") (pin "1") (pinfunction "1_1") (pintype "passive"))
      (node (ref "U5") (pin "6") (pinfunction "VOUT-_6") (pintype "passive"))
    )
    (net (code "75") (name "unconnected-(DA18-V--Pad5)") (class "Default")
      (node (ref "DA18") (pin "5") (pinfunction "V-_5") (pintype "passive"))
    )
    (net (code "76") (name "unconnected-(DA19-NC-Pad5)") (class "Default")
      (node (ref "DA19") (pin "5") (pinfunction "NC_5") (pintype "passive"))
    )
    (net (code "77") (name "unconnected-(DA19-NC-Pad8)") (class "Default")
      (node (ref "DA19") (pin "8") (pinfunction "NC_8") (pintype "passive"))
    )
    (net (code "78") (name "unconnected-(DA19-ON{slash}OFF-Pad3)") (class "Default")
      (node (ref "DA19") (pin "3") (pinfunction "ON/OFF_3") (pintype "passive"))
    )
    (net (code "79") (name "unconnected-(DD15-NC-Pad7)") (class "Default")
      (node (ref "DD15") (pin "7") (pinfunction "NC_7") (pintype "passive"))
    )
  )
)
